# 01_Power.net
KiCad netlist of a schematic drawn in Altium Designer
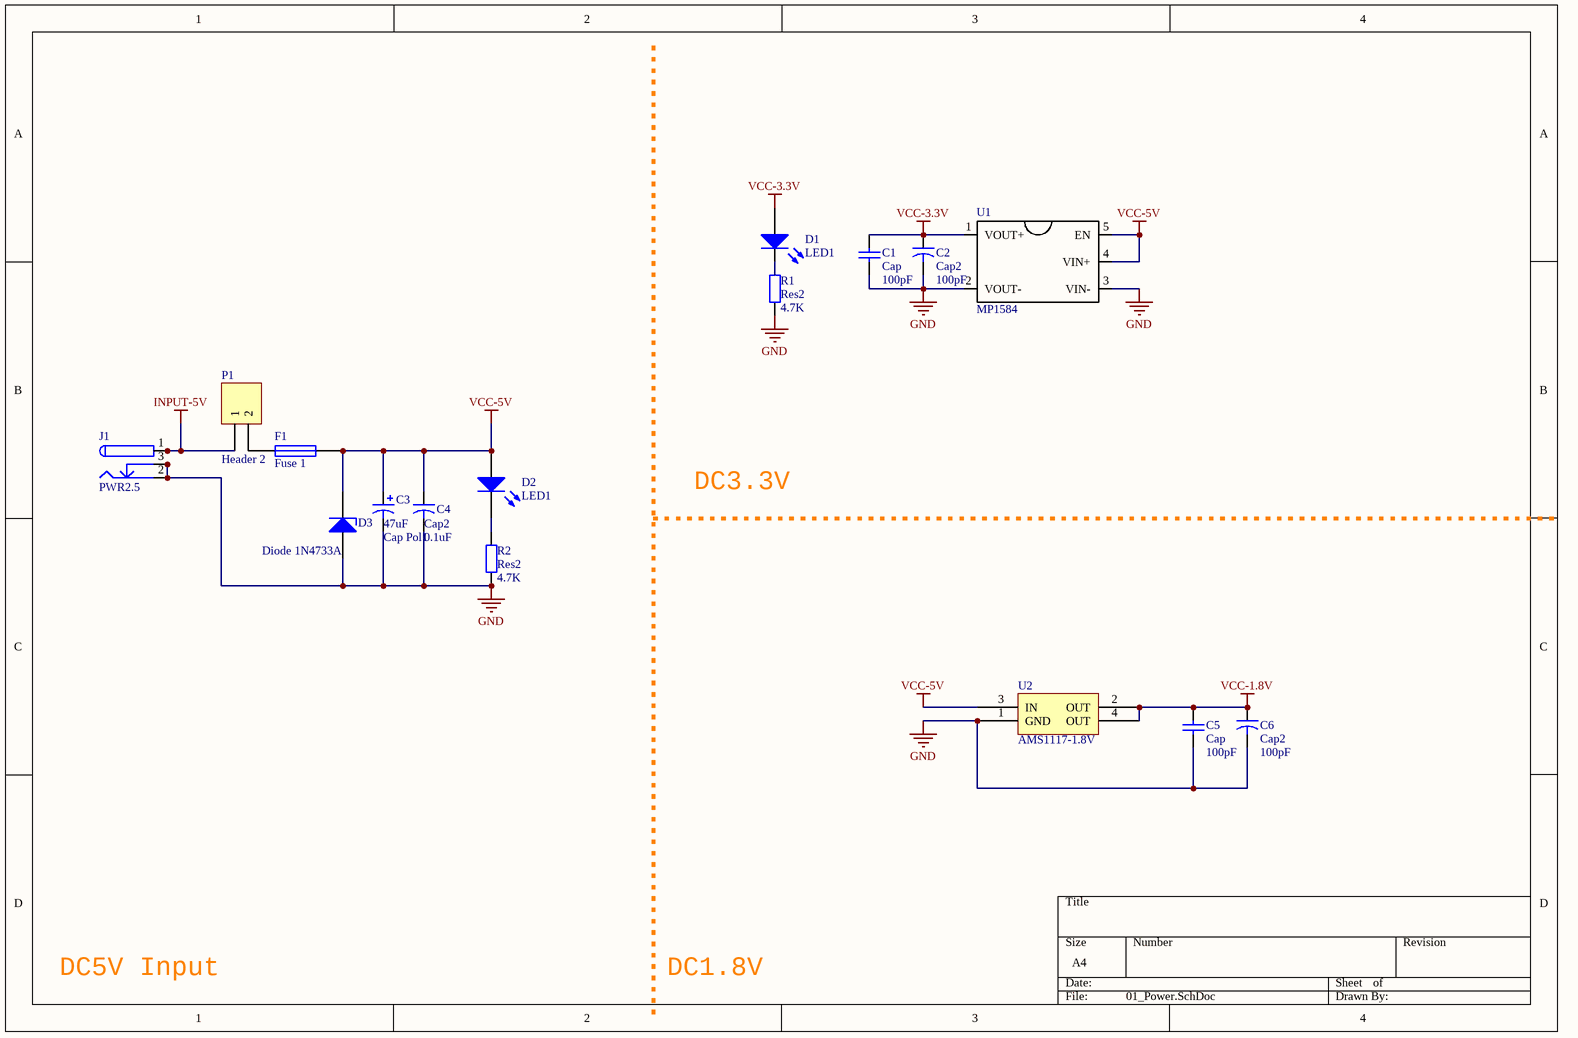
[diagram p0: 01_Power.SchDoc]

(export (version "E")
  (design (tool "Eeschema 10.0.6"))
  (components
    (comp (ref "C1")
      (value "Cap")
      (footprint "RAD-0.1")
      (description "Capacitor")
      (fields (field (name "ALTIUM_VALUE") "100pF") (field (name "PUBLISHER") "Altium Limited"))
      (libsource (lib "Miscellaneous Devices") (part "Cap"))
    )
    (comp (ref "C2")
      (value "Cap2")
      (footprint "CAPR5-4X5")
      (description "Capacitor")
      (fields (field (name "ALTIUM_VALUE") "100pF") (field (name "PUBLISHER") "Altium Limited"))
      (libsource (lib "Miscellaneous Devices") (part "Cap2"))
    )
    (comp (ref "C3")
      (value "Cap Pol1")
      (footprint "RB2.5-6.3")
      (description "Polarized Capacitor (Radial)")
      (fields (field (name "ALTIUM_VALUE") "47uF") (field (name "PUBLISHER") "Altium Limited"))
      (libsource (lib "Miscellaneous Devices") (part "Cap Pol1"))
    )
    (comp (ref "C4")
      (value "Cap2")
      (footprint "CAPR5-4X5")
      (description "Capacitor")
      (fields (field (name "ALTIUM_VALUE") "0.1uF") (field (name "PUBLISHER") "Altium Limited"))
      (libsource (lib "Miscellaneous Devices") (part "Cap2"))
    )
    (comp (ref "C5")
      (value "Cap")
      (footprint "RAD-0.1")
      (description "Capacitor")
      (fields (field (name "ALTIUM_VALUE") "100pF") (field (name "PUBLISHER") "Altium Limited"))
      (libsource (lib "Miscellaneous Devices") (part "Cap"))
    )
    (comp (ref "C6")
      (value "Cap2")
      (footprint "CAPR5-4X5")
      (description "Capacitor")
      (fields (field (name "ALTIUM_VALUE") "100pF") (field (name "PUBLISHER") "Altium Limited"))
      (libsource (lib "Miscellaneous Devices") (part "Cap2"))
    )
    (comp (ref "D1")
      (value "LED1")
      (footprint "LED-R3.0")
      (description "Typical RED GaAs LED")
      (fields (field (name "PUBLISHER") "Altium Limited"))
      (libsource (lib "Miscellaneous Devices") (part "LED1"))
    )
    (comp (ref "D2")
      (value "LED1")
      (footprint "LED-R3.0")
      (description "Typical RED GaAs LED")
      (fields (field (name "PUBLISHER") "Altium Limited"))
      (libsource (lib "Miscellaneous Devices") (part "LED1"))
    )
    (comp (ref "D3")
      (value "Diode 1N4733A")
      (footprint "DO-35")
      (description "DIODE ZENER 5.1V 1W DO41")
      (fields
        (field (name "MANUFACTURER") "Diodes")
        (field (name "MANUFACTURER PART NUMBER") "1N4733A-T")
        (field (name "PUBLISHER") "Altium Limited")
      )
      (libsource (lib "Miscellaneous Modules") (part "Diode 1N4733A"))
    )
    (comp (ref "F1")
      (value "Fuse 1")
      (footprint "PIN-W2/E2.8")
      (description "Fuse")
      (fields (field (name "PUBLISHER") "Altium Limited"))
      (libsource (lib "Miscellaneous Devices") (part "Fuse 1"))
    )
    (comp (ref "J1")
      (value "PWR2.5")
      (footprint "KLD-0202")
      (description "Low Voltage Power Supply Connector")
      (fields (field (name "PUBLISHER") "Altium Limited"))
      (libsource (lib "Miscellaneous Connectors") (part "PWR2.5"))
    )
    (comp (ref "P1")
      (value "Header 2")
      (footprint "HDR1X2")
      (description "Header, 2-Pin")
      (fields (field (name "PUBLISHER") "Altium Limited"))
      (libsource (lib "Miscellaneous Connectors") (part "Header 2"))
    )
    (comp (ref "R1")
      (value "Res2")
      (footprint "AXIAL-0.4")
      (description "Resistor")
      (fields (field (name "ALTIUM_VALUE") "4.7K") (field (name "PUBLISHER") "Altium Limited"))
      (libsource (lib "Miscellaneous Devices") (part "Res2"))
    )
    (comp (ref "R2")
      (value "Res2")
      (footprint "AXIAL-0.4")
      (description "Resistor")
      (fields (field (name "ALTIUM_VALUE") "4.7K") (field (name "PUBLISHER") "Altium Limited"))
      (libsource (lib "Miscellaneous Devices") (part "Res2"))
    )
    (comp (ref "U1")
      (value "MP1584")
      (footprint "Miscellaneous Modules:MP1584")
      (description "3.3V Voltage Regulators - Switching Regulators 3A 1.5MHz 28V Nonsync Buck")
      (fields
        (field (name "MANUFACTURER") "Monolithic Power Systems (MPS)")
        (field (name "MANUFACTURER PART NUMBER") "MP1584EN-LF")
      )
      (libsource (lib "Miscellaneous Modules") (part "MP1584"))
    )
    (comp (ref "U2")
      (value "AMS1117-1.8V")
      (footprint "SOT223-4M")
      (description "AM1117")
      (fields
        (field (name "MANUFACTURER") "STMicroelectronics")
        (field (name "MANUFACTURER PART NUMBER") "LD1117S-12TR")
      )
      (libsource (lib "Miscellaneous Modules") (part "AMS1117"))
    )
  )
  (nets
    (net (code "1") (name "GND") (class "Default")
      (node (ref "C1") (pin "1") (pinfunction "1_1") (pintype "passive"))
      (node (ref "C2") (pin "2") (pinfunction "2_2") (pintype "passive"))
      (node (ref "C3") (pin "2") (pinfunction "2_2") (pintype "passive"))
      (node (ref "C4") (pin "2") (pinfunction "2_2") (pintype "passive"))
      (node (ref "C5") (pin "1") (pinfunction "1_1") (pintype "passive"))
      (node (ref "C6") (pin "2") (pinfunction "2_2") (pintype "passive"))
      (node (ref "D3") (pin "1") (pinfunction "A_1") (pintype "passive"))
      (node (ref "J1") (pin "2") (pinfunction "2_2") (pintype "power_in"))
      (node (ref "J1") (pin "2A") (pinfunction "2A_2A") (pintype "power_in"))
      (node (ref "J1") (pin "2B") (pinfunction "2B_2B") (pintype "power_in"))
      (node (ref "J1") (pin "3") (pinfunction "3_3") (pintype "power_in"))
      (node (ref "J1") (pin "3A") (pinfunction "3A_3A") (pintype "power_in"))
      (node (ref "J1") (pin "3B") (pinfunction "3B_3B") (pintype "power_in"))
      (node (ref "R1") (pin "1") (pinfunction "1_1") (pintype "passive"))
      (node (ref "R2") (pin "1") (pinfunction "1_1") (pintype "passive"))
      (node (ref "U1") (pin "2") (pinfunction "VOUT-_2") (pintype "passive"))
      (node (ref "U1") (pin "3") (pinfunction "VIN-_3") (pintype "passive"))
      (node (ref "U2") (pin "1") (pinfunction "GND_1") (pintype "passive"))
    )
    (net (code "2") (name "INPUT-5V") (class "Default")
      (node (ref "J1") (pin "1") (pinfunction "1_1") (pintype "power_in"))
      (node (ref "J1") (pin "1A") (pinfunction "1A_1A") (pintype "power_in"))
      (node (ref "J1") (pin "1B") (pinfunction "1B_1B") (pintype "power_in"))
      (node (ref "P1") (pin "1") (pinfunction "1_1") (pintype "passive"))
    )
    (net (code "3") (name "Net-(D1-K)") (class "Default")
      (node (ref "D1") (pin "2") (pinfunction "K_2") (pintype "passive"))
      (node (ref "R1") (pin "2") (pinfunction "2_2") (pintype "passive"))
    )
    (net (code "4") (name "Net-(D2-K)") (class "Default")
      (node (ref "D2") (pin "2") (pinfunction "K_2") (pintype "passive"))
      (node (ref "R2") (pin "2") (pinfunction "2_2") (pintype "passive"))
    )
    (net (code "5") (name "Net-(F1-Pad1)") (class "Default")
      (node (ref "F1") (pin "1") (pinfunction "1_1") (pintype "passive"))
      (node (ref "P1") (pin "2") (pinfunction "2_2") (pintype "passive"))
    )
    (net (code "6") (name "VCC-1.8V") (class "Default")
      (node (ref "C5") (pin "2") (pinfunction "2_2") (pintype "passive"))
      (node (ref "C6") (pin "1") (pinfunction "1_1") (pintype "passive"))
      (node (ref "U2") (pin "2") (pinfunction "OUT_2") (pintype "passive"))
      (node (ref "U2") (pin "4") (pinfunction "OUT_4") (pintype "passive"))
    )
    (net (code "7") (name "VCC-3.3V") (class "Default")
      (node (ref "C1") (pin "2") (pinfunction "2_2") (pintype "passive"))
      (node (ref "C2") (pin "1") (pinfunction "1_1") (pintype "passive"))
      (node (ref "D1") (pin "1") (pinfunction "A_1") (pintype "passive"))
      (node (ref "U1") (pin "1") (pinfunction "VOUT+_1") (pintype "passive"))
    )
    (net (code "8") (name "VCC-5V") (class "Default")
      (node (ref "C3") (pin "1") (pinfunction "1_1") (pintype "passive"))
      (node (ref "C4") (pin "1") (pinfunction "1_1") (pintype "passive"))
      (node (ref "D2") (pin "1") (pinfunction "A_1") (pintype "passive"))
      (node (ref "D3") (pin "2") (pinfunction "K_2") (pintype "passive"))
      (node (ref "F1") (pin "2") (pinfunction "2_2") (pintype "passive"))
      (node (ref "U1") (pin "4") (pinfunction "VIN+_4") (pintype "passive"))
      (node (ref "U1") (pin "5") (pinfunction "EN_5") (pintype "passive"))
      (node (ref "U2") (pin "3") (pinfunction "IN_3") (pintype "passive"))
    )
  )
)
